# Esp_4relay_feedback.net
KiCad netlist of a schematic drawn in EAGLE
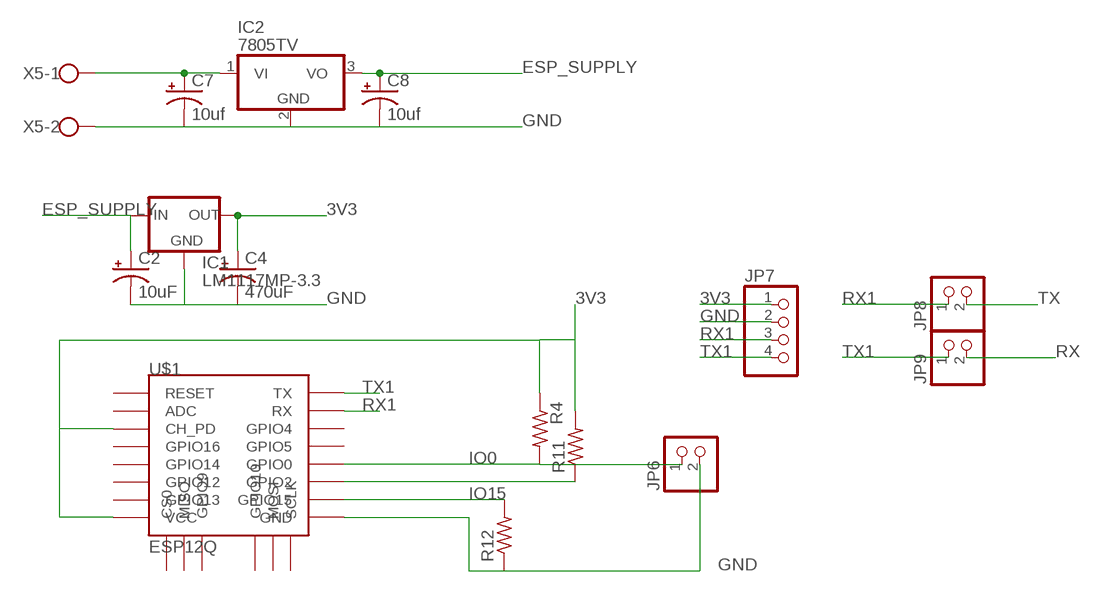
[diagram p0: schematic, sheet 1]
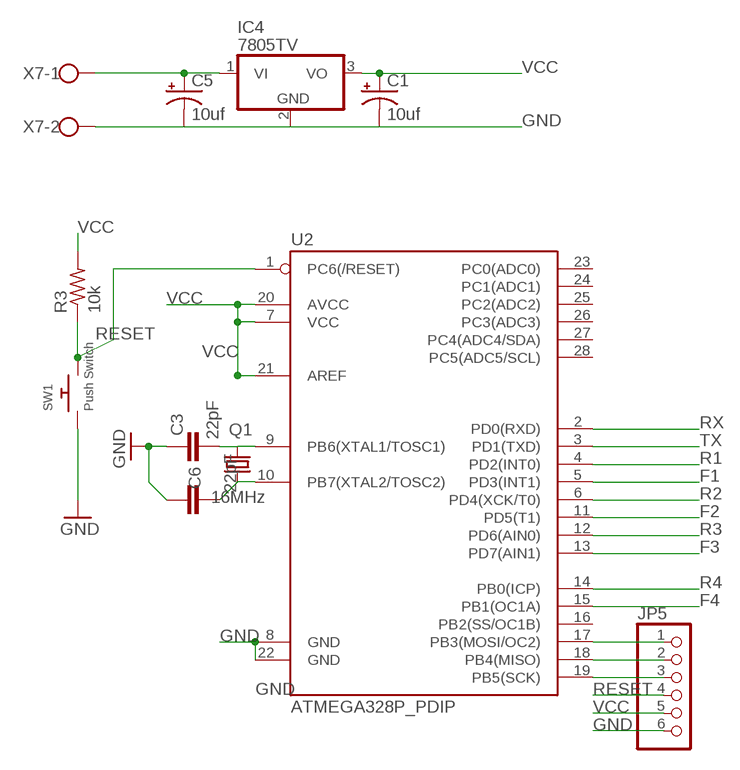
[diagram p1: schematic, sheet 2]
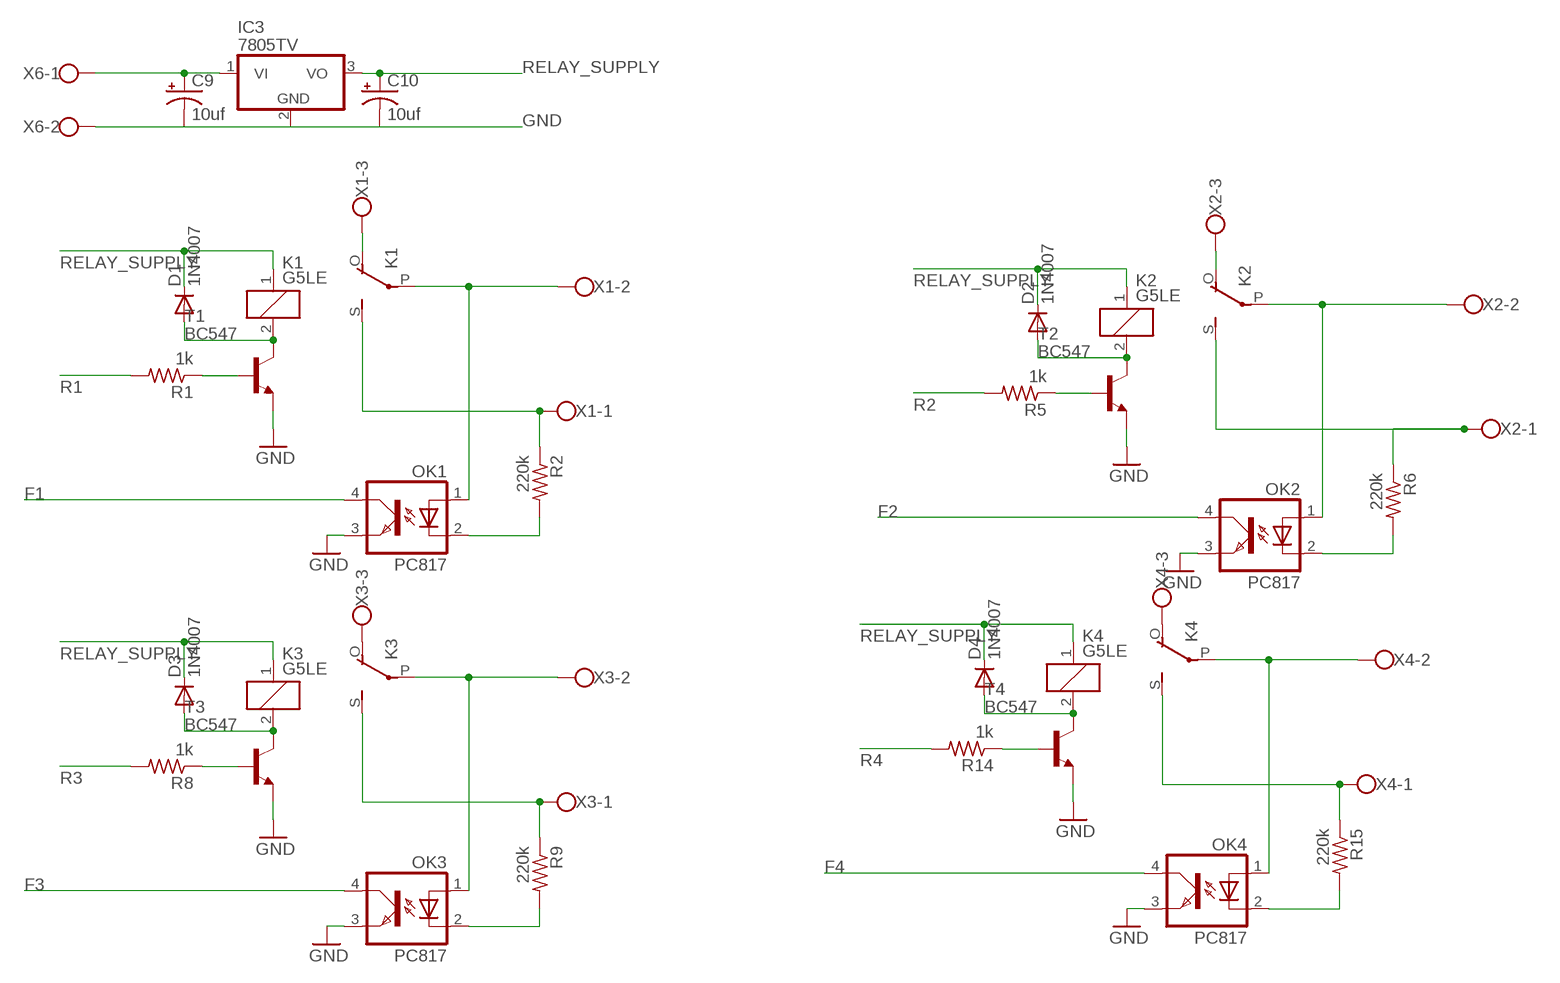
[diagram p2: schematic, sheet 3]

(export (version "E")
  (design (tool "Eeschema 10.0.6"))
  (components
    (comp (ref "C9")
      (value "10uf")
      (footprint "eagle-import:E2,5-6")
      (libsource (lib "eagle-import") (part "CPOL-USE2.5-6"))
    )
    (comp (ref "C10")
      (value "10uf")
      (footprint "eagle-import:E2,5-6")
      (libsource (lib "eagle-import") (part "CPOL-USE2.5-6"))
    )
    (comp (ref "D1")
      (value "1N4007")
      (footprint "eagle-import:DO41-10")
      (libsource (lib "eagle-import") (part "1N4004"))
    )
    (comp (ref "D2")
      (value "1N4007")
      (footprint "eagle-import:DO41-10")
      (libsource (lib "eagle-import") (part "1N4004"))
    )
    (comp (ref "D3")
      (value "1N4007")
      (footprint "eagle-import:DO41-10")
      (libsource (lib "eagle-import") (part "1N4004"))
    )
    (comp (ref "D4")
      (value "1N4007")
      (footprint "eagle-import:DO41-10")
      (libsource (lib "eagle-import") (part "1N4004"))
    )
    (comp (ref "IC3")
      (value "7805TV")
      (footprint "eagle-import:TO220V")
      (libsource (lib "eagle-import") (part "78TV05"))
    )
    (comp (ref "K1")
      (value "G5LE")
      (footprint "eagle-import:G5LE")
      (libsource (lib "eagle-import") (part "G5LE"))
    )
    (comp (ref "K2")
      (value "G5LE")
      (footprint "eagle-import:G5LE")
      (libsource (lib "eagle-import") (part "G5LE"))
    )
    (comp (ref "K3")
      (value "G5LE")
      (footprint "eagle-import:G5LE")
      (libsource (lib "eagle-import") (part "G5LE"))
    )
    (comp (ref "K4")
      (value "G5LE")
      (footprint "eagle-import:G5LE")
      (libsource (lib "eagle-import") (part "G5LE"))
    )
    (comp (ref "OK1")
      (value "PC817")
      (footprint "eagle-import:DIL04")
      (fields (field (name "MPN") "PC817X4J000F"))
      (libsource (lib "eagle-import") (part "PC817"))
    )
    (comp (ref "OK2")
      (value "PC817")
      (footprint "eagle-import:DIL04")
      (fields (field (name "MPN") "PC817X4J000F"))
      (libsource (lib "eagle-import") (part "PC817"))
    )
    (comp (ref "OK3")
      (value "PC817")
      (footprint "eagle-import:DIL04")
      (fields (field (name "MPN") "PC817X4J000F"))
      (libsource (lib "eagle-import") (part "PC817"))
    )
    (comp (ref "OK4")
      (value "PC817")
      (footprint "eagle-import:DIL04")
      (fields (field (name "MPN") "PC817X4J000F"))
      (libsource (lib "eagle-import") (part "PC817"))
    )
    (comp (ref "R1")
      (value "1k")
      (footprint "eagle-import:0207_10")
      (libsource (lib "eagle-import") (part "R-US_0207/10"))
    )
    (comp (ref "R2")
      (value "220k")
      (footprint "eagle-import:0207_10")
      (libsource (lib "eagle-import") (part "R-US_0207/10"))
    )
    (comp (ref "R5")
      (value "1k")
      (footprint "eagle-import:0207_10")
      (libsource (lib "eagle-import") (part "R-US_0207/10"))
    )
    (comp (ref "R6")
      (value "220k")
      (footprint "eagle-import:0207_10")
      (libsource (lib "eagle-import") (part "R-US_0207/10"))
    )
    (comp (ref "R8")
      (value "1k")
      (footprint "eagle-import:0207_10")
      (libsource (lib "eagle-import") (part "R-US_0207/10"))
    )
    (comp (ref "R9")
      (value "220k")
      (footprint "eagle-import:0207_10")
      (libsource (lib "eagle-import") (part "R-US_0207/10"))
    )
    (comp (ref "R14")
      (value "1k")
      (footprint "eagle-import:0207_10")
      (libsource (lib "eagle-import") (part "R-US_0207/10"))
    )
    (comp (ref "R15")
      (value "220k")
      (footprint "eagle-import:0207_10")
      (libsource (lib "eagle-import") (part "R-US_0207/10"))
    )
    (comp (ref "T1")
      (value "BC547")
      (footprint "eagle-import:TO92")
      (libsource (lib "eagle-import") (part "BC547"))
    )
    (comp (ref "T2")
      (value "BC547")
      (footprint "eagle-import:TO92")
      (libsource (lib "eagle-import") (part "BC547"))
    )
    (comp (ref "T3")
      (value "BC547")
      (footprint "eagle-import:TO92")
      (libsource (lib "eagle-import") (part "BC547"))
    )
    (comp (ref "T4")
      (value "BC547")
      (footprint "eagle-import:TO92")
      (libsource (lib "eagle-import") (part "BC547"))
    )
    (comp (ref "X1")
      (value "W237-103")
      (footprint "eagle-import:W237-103")
      (fields
        (field (name "MPN") "237-103")
        (field (name "MPN_1") "237-103")
        (field (name "OC_FARNELL") "unknown")
        (field (name "OC_NEWARK") "18M7116")
      )
      (libsource (lib "eagle-import") (part "W237-103"))
    )
    (comp (ref "X2")
      (value "W237-103")
      (footprint "eagle-import:W237-103")
      (fields
        (field (name "MPN") "237-103")
        (field (name "MPN_1") "237-103")
        (field (name "OC_FARNELL") "unknown")
        (field (name "OC_NEWARK") "18M7116")
      )
      (libsource (lib "eagle-import") (part "W237-103"))
    )
    (comp (ref "X3")
      (value "W237-103")
      (footprint "eagle-import:W237-103")
      (fields
        (field (name "MPN") "237-103")
        (field (name "MPN_1") "237-103")
        (field (name "OC_FARNELL") "unknown")
        (field (name "OC_NEWARK") "18M7116")
      )
      (libsource (lib "eagle-import") (part "W237-103"))
    )
    (comp (ref "X4")
      (value "W237-103")
      (footprint "eagle-import:W237-103")
      (fields
        (field (name "MPN") "237-103")
        (field (name "MPN_1") "237-103")
        (field (name "OC_FARNELL") "unknown")
        (field (name "OC_NEWARK") "18M7116")
      )
      (libsource (lib "eagle-import") (part "W237-103"))
    )
    (comp (ref "X6")
      (value "W237-102")
      (footprint "eagle-import:W237-102")
      (fields (field (name "MPN") "237-102"))
      (libsource (lib "eagle-import") (part "W237-102"))
    )
    (comp (ref "C2")
      (value "10uF")
      (footprint "eagle-import:E2,5-6")
      (libsource (lib "eagle-import") (part "CPOL-USE2.5-6"))
    )
    (comp (ref "C4")
      (value "470uF")
      (footprint "eagle-import:E5-8,5")
      (libsource (lib "eagle-import") (part "CPOL-USE5-8.5"))
    )
    (comp (ref "C7")
      (value "10uf")
      (footprint "eagle-import:E2,5-6")
      (libsource (lib "eagle-import") (part "CPOL-USE2.5-6"))
    )
    (comp (ref "C8")
      (value "10uf")
      (footprint "eagle-import:E2,5-6")
      (libsource (lib "eagle-import") (part "CPOL-USE2.5-6"))
    )
    (comp (ref "IC1")
      (value "LM1117MP-3.3")
      (footprint "eagle-import:SOT223")
      (fields (field (name "MF") "Texas Instruments"))
      (libsource (lib "eagle-import") (part "LM1117?-MP3.3"))
    )
    (comp (ref "IC2")
      (value "7805TV")
      (footprint "eagle-import:TO220V")
      (libsource (lib "eagle-import") (part "78TV05"))
    )
    (comp (ref "JP6")
      (value "PINHD-1X2")
      (footprint "eagle-import:1X02")
      (libsource (lib "eagle-import") (part "PINHD-1X2"))
    )
    (comp (ref "JP7")
      (value "PINHD-1X4")
      (footprint "eagle-import:1X04")
      (libsource (lib "eagle-import") (part "PINHD-1X4"))
    )
    (comp (ref "JP8")
      (value "PINHD-1X2")
      (footprint "eagle-import:1X02")
      (libsource (lib "eagle-import") (part "PINHD-1X2"))
    )
    (comp (ref "JP9")
      (value "PINHD-1X2")
      (footprint "eagle-import:1X02")
      (libsource (lib "eagle-import") (part "PINHD-1X2"))
    )
    (comp (ref "R4")
      (value "R-US_0207/10")
      (footprint "eagle-import:0207_10")
      (libsource (lib "eagle-import") (part "R-US_0207/10"))
    )
    (comp (ref "R11")
      (value "R-US_0207/10")
      (footprint "eagle-import:0207_10")
      (libsource (lib "eagle-import") (part "R-US_0207/10"))
    )
    (comp (ref "R12")
      (value "R-US_0207/10")
      (footprint "eagle-import:0207_10")
      (libsource (lib "eagle-import") (part "R-US_0207/10"))
    )
    (comp (ref "U$1")
      (value "ESP12Q")
      (footprint "eagle-import:ESP12Q")
      (libsource (lib "eagle-import") (part "ESP12Q"))
    )
    (comp (ref "X5")
      (value "W237-102")
      (footprint "eagle-import:W237-102")
      (fields (field (name "MPN") "237-102"))
      (libsource (lib "eagle-import") (part "W237-102"))
    )
    (comp (ref "C1")
      (value "10uf")
      (footprint "eagle-import:E2,5-6")
      (libsource (lib "eagle-import") (part "CPOL-USE2.5-6"))
    )
    (comp (ref "C3")
      (value "22pF")
      (footprint "eagle-import:CAP-PTH-SMALL")
      (libsource (lib "eagle-import") (part "CAPPTH"))
    )
    (comp (ref "C5")
      (value "10uf")
      (footprint "eagle-import:E2,5-6")
      (libsource (lib "eagle-import") (part "CPOL-USE2.5-6"))
    )
    (comp (ref "C6")
      (value "22pF")
      (footprint "eagle-import:CAP-PTH-SMALL")
      (libsource (lib "eagle-import") (part "CAPPTH"))
    )
    (comp (ref "IC4")
      (value "7805TV")
      (footprint "eagle-import:TO220V")
      (libsource (lib "eagle-import") (part "78TV05"))
    )
    (comp (ref "JP5")
      (value "PINHD-1X6")
      (footprint "eagle-import:1X06")
      (libsource (lib "eagle-import") (part "PINHD-1X6"))
    )
    (comp (ref "Q1")
      (value "16MHz")
      (footprint "eagle-import:HC49US")
      (libsource (lib "eagle-import") (part "CRYSTALHC49US"))
    )
    (comp (ref "R3")
      (value "10k")
      (footprint "eagle-import:0207_10")
      (libsource (lib "eagle-import") (part "resistor_R-US_0207/10"))
    )
    (comp (ref "SW1")
      (value "Push Switch")
      (footprint "eagle-import:TACT_PANA-EVQ")
      (libsource (lib "eagle-import") (part "SWITCH_PUSHBUTTONEVQ-PE"))
    )
    (comp (ref "U2")
      (value "ATMEGA328P_PDIP")
      (footprint "eagle-import:DIL28-3")
      (libsource (lib "eagle-import") (part "ATMEGA328P_PDIP"))
    )
    (comp (ref "X7")
      (value "W237-102")
      (footprint "eagle-import:W237-102")
      (fields (field (name "MPN") "237-102"))
      (libsource (lib "eagle-import") (part "W237-102"))
    )
  )
  (nets
    (net (code "1") (name "3V3") (class "Default")
      (node (ref "C4") (pin "+") (pinfunction "+_+") (pintype "passive"))
      (node (ref "IC1") (pin "2") (pinfunction "OUT_2") (pintype "passive"))
      (node (ref "IC1") (pin "4") (pinfunction "OUT_4") (pintype "passive"))
      (node (ref "JP7") (pin "1") (pinfunction "1_1") (pintype "passive"))
      (node (ref "R11") (pin "2") (pinfunction "2_2") (pintype "passive"))
      (node (ref "R4") (pin "1") (pinfunction "1_1") (pintype "passive"))
      (node (ref "U$1") (pin "CH_PD") (pinfunction "CH_PD_CH_PD") (pintype "bidirectional"))
      (node (ref "U$1") (pin "VCC") (pinfunction "VCC_VCC") (pintype "bidirectional"))
    )
    (net (code "2") (name "ESP_SUPPLY") (class "Default")
      (node (ref "C2") (pin "+") (pinfunction "+_+") (pintype "passive"))
      (node (ref "C8") (pin "+") (pinfunction "+_+") (pintype "passive"))
      (node (ref "IC1") (pin "3") (pinfunction "IN_3") (pintype "input"))
      (node (ref "IC2") (pin "3") (pinfunction "VO_3") (pintype "passive"))
    )
    (net (code "3") (name "F1") (class "Default")
      (node (ref "OK1") (pin "4") (pinfunction "COL_4") (pintype "passive"))
      (node (ref "U2") (pin "5") (pinfunction "PD3(INT1)_5") (pintype "bidirectional"))
    )
    (net (code "4") (name "F2") (class "Default")
      (node (ref "OK2") (pin "4") (pinfunction "COL_4") (pintype "passive"))
      (node (ref "U2") (pin "11") (pinfunction "PD5(T1)_11") (pintype "bidirectional"))
    )
    (net (code "5") (name "F3") (class "Default")
      (node (ref "OK3") (pin "4") (pinfunction "COL_4") (pintype "passive"))
      (node (ref "U2") (pin "13") (pinfunction "PD7(AIN1)_13") (pintype "bidirectional"))
    )
    (net (code "6") (name "F4") (class "Default")
      (node (ref "OK4") (pin "4") (pinfunction "COL_4") (pintype "passive"))
      (node (ref "U2") (pin "15") (pinfunction "PB1(OC1A)_15") (pintype "bidirectional"))
    )
    (net (code "7") (name "GND") (class "Default")
      (node (ref "C1") (pin "-") (pinfunction "-_-") (pintype "passive"))
      (node (ref "C10") (pin "-") (pinfunction "-_-") (pintype "passive"))
      (node (ref "C2") (pin "-") (pinfunction "-_-") (pintype "passive"))
      (node (ref "C3") (pin "1") (pinfunction "1_1") (pintype "passive"))
      (node (ref "C4") (pin "-") (pinfunction "-_-") (pintype "passive"))
      (node (ref "C5") (pin "-") (pinfunction "-_-") (pintype "passive"))
      (node (ref "C6") (pin "1") (pinfunction "1_1") (pintype "passive"))
      (node (ref "C7") (pin "-") (pinfunction "-_-") (pintype "passive"))
      (node (ref "C8") (pin "-") (pinfunction "-_-") (pintype "passive"))
      (node (ref "C9") (pin "-") (pinfunction "-_-") (pintype "passive"))
      (node (ref "IC1") (pin "1") (pinfunction "GND_1") (pintype "input"))
      (node (ref "IC2") (pin "2") (pinfunction "GND_2") (pintype "passive"))
      (node (ref "IC3") (pin "2") (pinfunction "GND_2") (pintype "passive"))
      (node (ref "IC4") (pin "2") (pinfunction "GND_2") (pintype "passive"))
      (node (ref "JP5") (pin "6") (pinfunction "6_6") (pintype "passive"))
      (node (ref "JP6") (pin "2") (pinfunction "2_2") (pintype "passive"))
      (node (ref "JP7") (pin "2") (pinfunction "2_2") (pintype "passive"))
      (node (ref "OK1") (pin "3") (pinfunction "EMIT_3") (pintype "passive"))
      (node (ref "OK2") (pin "3") (pinfunction "EMIT_3") (pintype "passive"))
      (node (ref "OK3") (pin "3") (pinfunction "EMIT_3") (pintype "passive"))
      (node (ref "OK4") (pin "3") (pinfunction "EMIT_3") (pintype "passive"))
      (node (ref "R12") (pin "1") (pinfunction "1_1") (pintype "passive"))
      (node (ref "SW1") (pin "P$1") (pinfunction "P$1_P$1") (pintype "passive"))
      (node (ref "T1") (pin "1") (pinfunction "E_1") (pintype "passive"))
      (node (ref "T2") (pin "1") (pinfunction "E_1") (pintype "passive"))
      (node (ref "T3") (pin "1") (pinfunction "E_1") (pintype "passive"))
      (node (ref "T4") (pin "1") (pinfunction "E_1") (pintype "passive"))
      (node (ref "U$1") (pin "GND") (pinfunction "GND_GND") (pintype "bidirectional"))
      (node (ref "U2") (pin "22") (pinfunction "GND_22") (pintype "bidirectional"))
      (node (ref "U2") (pin "8") (pinfunction "GND_8") (pintype "bidirectional"))
      (node (ref "X5") (pin "2") (pinfunction "KL_2") (pintype "passive"))
      (node (ref "X6") (pin "2") (pinfunction "KL_2") (pintype "passive"))
      (node (ref "X7") (pin "2") (pinfunction "KL_2") (pintype "passive"))
    )
    (net (code "8") (name "IO0") (class "Default")
      (node (ref "JP6") (pin "1") (pinfunction "1_1") (pintype "passive"))
      (node (ref "R4") (pin "2") (pinfunction "2_2") (pintype "passive"))
      (node (ref "U$1") (pin "GPIO0") (pinfunction "GPIO0_GPIO0") (pintype "bidirectional"))
    )
    (net (code "9") (name "IO15") (class "Default")
      (node (ref "R12") (pin "2") (pinfunction "2_2") (pintype "passive"))
      (node (ref "U$1") (pin "GPIO15") (pinfunction "GPIO15_GPIO15") (pintype "bidirectional"))
    )
    (net (code "10") (name "Net-(IC2-VI)") (class "Default")
      (node (ref "C7") (pin "+") (pinfunction "+_+") (pintype "passive"))
      (node (ref "IC2") (pin "1") (pinfunction "VI_1") (pintype "input"))
      (node (ref "X5") (pin "1") (pinfunction "KL_1") (pintype "passive"))
    )
    (net (code "11") (name "Net-(IC3-VI)") (class "Default")
      (node (ref "C9") (pin "+") (pinfunction "+_+") (pintype "passive"))
      (node (ref "IC3") (pin "1") (pinfunction "VI_1") (pintype "input"))
      (node (ref "X6") (pin "1") (pinfunction "KL_1") (pintype "passive"))
    )
    (net (code "12") (name "Net-(IC4-VI)") (class "Default")
      (node (ref "C5") (pin "+") (pinfunction "+_+") (pintype "passive"))
      (node (ref "IC4") (pin "1") (pinfunction "VI_1") (pintype "input"))
      (node (ref "X7") (pin "1") (pinfunction "KL_1") (pintype "passive"))
    )
    (net (code "13") (name "Net-(OK1-A)") (class "Default")
      (node (ref "K1") (pin "P") (pinfunction "P_P") (pintype "passive"))
      (node (ref "OK1") (pin "1") (pinfunction "A_1") (pintype "passive"))
      (node (ref "X1") (pin "2") (pinfunction "KL_2") (pintype "passive"))
    )
    (net (code "14") (name "Net-(OK1-C)") (class "Default")
      (node (ref "OK1") (pin "2") (pinfunction "C_2") (pintype "passive"))
      (node (ref "R2") (pin "2") (pinfunction "2_2") (pintype "passive"))
    )
    (net (code "15") (name "Net-(OK2-A)") (class "Default")
      (node (ref "K2") (pin "P") (pinfunction "P_P") (pintype "passive"))
      (node (ref "OK2") (pin "1") (pinfunction "A_1") (pintype "passive"))
      (node (ref "X2") (pin "2") (pinfunction "KL_2") (pintype "passive"))
    )
    (net (code "16") (name "Net-(OK2-C)") (class "Default")
      (node (ref "OK2") (pin "2") (pinfunction "C_2") (pintype "passive"))
      (node (ref "R6") (pin "2") (pinfunction "2_2") (pintype "passive"))
    )
    (net (code "17") (name "Net-(OK3-A)") (class "Default")
      (node (ref "K3") (pin "P") (pinfunction "P_P") (pintype "passive"))
      (node (ref "OK3") (pin "1") (pinfunction "A_1") (pintype "passive"))
      (node (ref "X3") (pin "2") (pinfunction "KL_2") (pintype "passive"))
    )
    (net (code "18") (name "Net-(OK3-C)") (class "Default")
      (node (ref "OK3") (pin "2") (pinfunction "C_2") (pintype "passive"))
      (node (ref "R9") (pin "2") (pinfunction "2_2") (pintype "passive"))
    )
    (net (code "19") (name "Net-(OK4-A)") (class "Default")
      (node (ref "K4") (pin "P") (pinfunction "P_P") (pintype "passive"))
      (node (ref "OK4") (pin "1") (pinfunction "A_1") (pintype "passive"))
      (node (ref "X4") (pin "2") (pinfunction "KL_2") (pintype "passive"))
    )
    (net (code "20") (name "Net-(OK4-C)") (class "Default")
      (node (ref "OK4") (pin "2") (pinfunction "C_2") (pintype "passive"))
      (node (ref "R15") (pin "2") (pinfunction "2_2") (pintype "passive"))
    )
    (net (code "21") (name "Net-(R11-Pad1)") (class "Default")
      (node (ref "R11") (pin "1") (pinfunction "1_1") (pintype "passive"))
      (node (ref "U$1") (pin "GPIO2") (pinfunction "GPIO2_GPIO2") (pintype "bidirectional"))
    )
    (net (code "22") (name "Net-(T1-B)") (class "Default")
      (node (ref "R1") (pin "1") (pinfunction "1_1") (pintype "passive"))
      (node (ref "T1") (pin "2") (pinfunction "B_2") (pintype "passive"))
    )
    (net (code "23") (name "Net-(T1-C)") (class "Default")
      (node (ref "D1") (pin "A") (pinfunction "A_A") (pintype "passive"))
      (node (ref "K1") (pin "2") (pinfunction "2_2") (pintype "passive"))
      (node (ref "T1") (pin "3") (pinfunction "C_3") (pintype "passive"))
    )
    (net (code "24") (name "Net-(T2-B)") (class "Default")
      (node (ref "R5") (pin "1") (pinfunction "1_1") (pintype "passive"))
      (node (ref "T2") (pin "2") (pinfunction "B_2") (pintype "passive"))
    )
    (net (code "25") (name "Net-(T2-C)") (class "Default")
      (node (ref "D2") (pin "A") (pinfunction "A_A") (pintype "passive"))
      (node (ref "K2") (pin "2") (pinfunction "2_2") (pintype "passive"))
      (node (ref "T2") (pin "3") (pinfunction "C_3") (pintype "passive"))
    )
    (net (code "26") (name "Net-(T3-B)") (class "Default")
      (node (ref "R8") (pin "1") (pinfunction "1_1") (pintype "passive"))
      (node (ref "T3") (pin "2") (pinfunction "B_2") (pintype "passive"))
    )
    (net (code "27") (name "Net-(T3-C)") (class "Default")
      (node (ref "D3") (pin "A") (pinfunction "A_A") (pintype "passive"))
      (node (ref "K3") (pin "2") (pinfunction "2_2") (pintype "passive"))
      (node (ref "T3") (pin "3") (pinfunction "C_3") (pintype "passive"))
    )
    (net (code "28") (name "Net-(T4-B)") (class "Default")
      (node (ref "R14") (pin "1") (pinfunction "1_1") (pintype "passive"))
      (node (ref "T4") (pin "2") (pinfunction "B_2") (pintype "passive"))
    )
    (net (code "29") (name "Net-(T4-C)") (class "Default")
      (node (ref "D4") (pin "A") (pinfunction "A_A") (pintype "passive"))
      (node (ref "K4") (pin "2") (pinfunction "2_2") (pintype "passive"))
      (node (ref "T4") (pin "3") (pinfunction "C_3") (pintype "passive"))
    )
    (net (code "30") (name "Net-(U2-PB3(MOSI{slash}OC2))") (class "Default")
      (node (ref "JP5") (pin "1") (pinfunction "1_1") (pintype "passive"))
      (node (ref "U2") (pin "17") (pinfunction "PB3(MOSI/OC2)_17") (pintype "bidirectional"))
    )
    (net (code "31") (name "Net-(U2-PB4(MISO))") (class "Default")
      (node (ref "JP5") (pin "2") (pinfunction "2_2") (pintype "passive"))
      (node (ref "U2") (pin "18") (pinfunction "PB4(MISO)_18") (pintype "bidirectional"))
    )
    (net (code "32") (name "Net-(U2-PB5(SCK))") (class "Default")
      (node (ref "JP5") (pin "3") (pinfunction "3_3") (pintype "passive"))
      (node (ref "U2") (pin "19") (pinfunction "PB5(SCK)_19") (pintype "bidirectional"))
    )
    (net (code "33") (name "Net-(U2-PB6(XTAL1{slash}TOSC1))") (class "Default")
      (node (ref "C3") (pin "2") (pinfunction "2_2") (pintype "passive"))
      (node (ref "Q1") (pin "2") (pinfunction "2_2") (pintype "passive"))
      (node (ref "U2") (pin "9") (pinfunction "PB6(XTAL1/TOSC1)_9") (pintype "bidirectional"))
    )
    (net (code "34") (name "Net-(U2-PB7(XTAL2{slash}TOSC2))") (class "Default")
      (node (ref "C6") (pin "2") (pinfunction "2_2") (pintype "passive"))
      (node (ref "Q1") (pin "1") (pinfunction "1_1") (pintype "passive"))
      (node (ref "U2") (pin "10") (pinfunction "PB7(XTAL2/TOSC2)_10") (pintype "bidirectional"))
    )
    (net (code "35") (name "Net-(X1A-KL)") (class "Default")
      (node (ref "K1") (pin "S") (pinfunction "S_S") (pintype "passive"))
      (node (ref "R2") (pin "1") (pinfunction "1_1") (pintype "passive"))
      (node (ref "X1") (pin "1") (pinfunction "KL_1") (pintype "passive"))
    )
    (net (code "36") (name "Net-(X1C-KL)") (class "Default")
      (node (ref "K1") (pin "O") (pinfunction "O_O") (pintype "passive"))
      (node (ref "X1") (pin "3") (pinfunction "KL_3") (pintype "passive"))
    )
    (net (code "37") (name "Net-(X2A-KL)") (class "Default")
      (node (ref "K2") (pin "S") (pinfunction "S_S") (pintype "passive"))
      (node (ref "R6") (pin "1") (pinfunction "1_1") (pintype "passive"))
      (node (ref "X2") (pin "1") (pinfunction "KL_1") (pintype "passive"))
    )
    (net (code "38") (name "Net-(X2C-KL)") (class "Default")
      (node (ref "K2") (pin "O") (pinfunction "O_O") (pintype "passive"))
      (node (ref "X2") (pin "3") (pinfunction "KL_3") (pintype "passive"))
    )
    (net (code "39") (name "Net-(X3A-KL)") (class "Default")
      (node (ref "K3") (pin "S") (pinfunction "S_S") (pintype "passive"))
      (node (ref "R9") (pin "1") (pinfunction "1_1") (pintype "passive"))
      (node (ref "X3") (pin "1") (pinfunction "KL_1") (pintype "passive"))
    )
    (net (code "40") (name "Net-(X3C-KL)") (class "Default")
      (node (ref "K3") (pin "O") (pinfunction "O_O") (pintype "passive"))
      (node (ref "X3") (pin "3") (pinfunction "KL_3") (pintype "passive"))
    )
    (net (code "41") (name "Net-(X4A-KL)") (class "Default")
      (node (ref "K4") (pin "S") (pinfunction "S_S") (pintype "passive"))
      (node (ref "R15") (pin "1") (pinfunction "1_1") (pintype "passive"))
      (node (ref "X4") (pin "1") (pinfunction "KL_1") (pintype "passive"))
    )
    (net (code "42") (name "Net-(X4C-KL)") (class "Default")
      (node (ref "K4") (pin "O") (pinfunction "O_O") (pintype "passive"))
      (node (ref "X4") (pin "3") (pinfunction "KL_3") (pintype "passive"))
    )
    (net (code "43") (name "R1") (class "Default")
      (node (ref "R1") (pin "2") (pinfunction "2_2") (pintype "passive"))
      (node (ref "U2") (pin "4") (pinfunction "PD2(INT0)_4") (pintype "bidirectional"))
    )
    (net (code "44") (name "R2") (class "Default")
      (node (ref "R5") (pin "2") (pinfunction "2_2") (pintype "passive"))
      (node (ref "U2") (pin "6") (pinfunction "PD4(XCK/T0)_6") (pintype "bidirectional"))
    )
    (net (code "45") (name "R3") (class "Default")
      (node (ref "R8") (pin "2") (pinfunction "2_2") (pintype "passive"))
      (node (ref "U2") (pin "12") (pinfunction "PD6(AIN0)_12") (pintype "bidirectional"))
    )
    (net (code "46") (name "R4") (class "Default")
      (node (ref "R14") (pin "2") (pinfunction "2_2") (pintype "passive"))
      (node (ref "U2") (pin "14") (pinfunction "PB0(ICP)_14") (pintype "bidirectional"))
    )
    (net (code "47") (name "RELAY_SUPPLY") (class "Default")
      (node (ref "C10") (pin "+") (pinfunction "+_+") (pintype "passive"))
      (node (ref "D1") (pin "C") (pinfunction "C_C") (pintype "passive"))
      (node (ref "D2") (pin "C") (pinfunction "C_C") (pintype "passive"))
      (node (ref "D3") (pin "C") (pinfunction "C_C") (pintype "passive"))
      (node (ref "D4") (pin "C") (pinfunction "C_C") (pintype "passive"))
      (node (ref "IC3") (pin "3") (pinfunction "VO_3") (pintype "passive"))
      (node (ref "K1") (pin "1") (pinfunction "1_1") (pintype "passive"))
      (node (ref "K2") (pin "1") (pinfunction "1_1") (pintype "passive"))
      (node (ref "K3") (pin "1") (pinfunction "1_1") (pintype "passive"))
      (node (ref "K4") (pin "1") (pinfunction "1_1") (pintype "passive"))
    )
    (net (code "48") (name "RESET") (class "Default")
      (node (ref "JP5") (pin "4") (pinfunction "4_4") (pintype "passive"))
      (node (ref "R3") (pin "1") (pinfunction "1_1") (pintype "passive"))
      (node (ref "SW1") (pin "P$2") (pinfunction "P$2_P$2") (pintype "passive"))
      (node (ref "U2") (pin "1") (pinfunction "PC6(/RESET)_1") (pintype "bidirectional"))
    )
    (net (code "49") (name "RX") (class "Default")
      (node (ref "JP9") (pin "2") (pinfunction "2_2") (pintype "passive"))
      (node (ref "U2") (pin "2") (pinfunction "PD0(RXD)_2") (pintype "bidirectional"))
    )
    (net (code "50") (name "RX1") (class "Default")
      (node (ref "JP7") (pin "3") (pinfunction "3_3") (pintype "passive"))
      (node (ref "JP8") (pin "1") (pinfunction "1_1") (pintype "passive"))
      (node (ref "U$1") (pin "RX") (pinfunction "RX_RX") (pintype "bidirectional"))
    )
    (net (code "51") (name "TX") (class "Default")
      (node (ref "JP8") (pin "2") (pinfunction "2_2") (pintype "passive"))
      (node (ref "U2") (pin "3") (pinfunction "PD1(TXD)_3") (pintype "bidirectional"))
    )
    (net (code "52") (name "TX1") (class "Default")
      (node (ref "JP7") (pin "4") (pinfunction "4_4") (pintype "passive"))
      (node (ref "JP9") (pin "1") (pinfunction "1_1") (pintype "passive"))
      (node (ref "U$1") (pin "TX") (pinfunction "TX_TX") (pintype "bidirectional"))
    )
    (net (code "53") (name "VCC") (class "Default")
      (node (ref "C1") (pin "+") (pinfunction "+_+") (pintype "passive"))
      (node (ref "IC4") (pin "3") (pinfunction "VO_3") (pintype "passive"))
      (node (ref "JP5") (pin "5") (pinfunction "5_5") (pintype "passive"))
      (node (ref "R3") (pin "2") (pinfunction "2_2") (pintype "passive"))
      (node (ref "U2") (pin "20") (pinfunction "AVCC_20") (pintype "bidirectional"))
      (node (ref "U2") (pin "21") (pinfunction "AREF_21") (pintype "bidirectional"))
      (node (ref "U2") (pin "7") (pinfunction "VCC_7") (pintype "bidirectional"))
    )
    (net (code "54") (name "unconnected-(U$1-PadADC)") (class "Default")
      (node (ref "U$1") (pin "ADC") (pinfunction "ADC_ADC") (pintype "bidirectional"))
    )
    (net (code "55") (name "unconnected-(U$1-PadCS0)") (class "Default")
      (node (ref "U$1") (pin "CS0") (pinfunction "CS0_CS0") (pintype "bidirectional"))
    )
    (net (code "56") (name "unconnected-(U$1-PadGPIO4)") (class "Default")
      (node (ref "U$1") (pin "GPIO4") (pinfunction "GPIO4_GPIO4") (pintype "bidirectional"))
    )
    (net (code "57") (name "unconnected-(U$1-PadGPIO5)") (class "Default")
      (node (ref "U$1") (pin "GPIO5") (pinfunction "GPIO5_GPIO5") (pintype "bidirectional"))
    )
    (net (code "58") (name "unconnected-(U$1-PadGPIO9)") (class "Default")
      (node (ref "U$1") (pin "GPIO9") (pinfunction "GPIO9_GPIO9") (pintype "bidirectional"))
    )
    (net (code "59") (name "unconnected-(U$1-PadGPIO10)") (class "Default")
      (node (ref "U$1") (pin "GPIO10") (pinfunction "GPIO10_GPIO10") (pintype "bidirectional"))
    )
    (net (code "60") (name "unconnected-(U$1-PadGPIO12)") (class "Default")
      (node (ref "U$1") (pin "GPIO12") (pinfunction "GPIO12_GPIO12") (pintype "bidirectional"))
    )
    (net (code "61") (name "unconnected-(U$1-PadGPIO13)") (class "Default")
      (node (ref "U$1") (pin "GPIO13") (pinfunction "GPIO13_GPIO13") (pintype "bidirectional"))
    )
    (net (code "62") (name "unconnected-(U$1-PadGPIO14)") (class "Default")
      (node (ref "U$1") (pin "GPIO14") (pinfunction "GPIO14_GPIO14") (pintype "bidirectional"))
    )
    (net (code "63") (name "unconnected-(U$1-PadGPIO16)") (class "Default")
      (node (ref "U$1") (pin "GPIO16") (pinfunction "GPIO16_GPIO16") (pintype "bidirectional"))
    )
    (net (code "64") (name "unconnected-(U$1-PadMISO)") (class "Default")
      (node (ref "U$1") (pin "MISO") (pinfunction "MISO_MISO") (pintype "bidirectional"))
    )
    (net (code "65") (name "unconnected-(U$1-PadMOSI)") (class "Default")
      (node (ref "U$1") (pin "MOSI") (pinfunction "MOSI_MOSI") (pintype "bidirectional"))
    )
    (net (code "66") (name "unconnected-(U$1-PadRESET)") (class "Default")
      (node (ref "U$1") (pin "RESET") (pinfunction "RESET_RESET") (pintype "bidirectional"))
    )
    (net (code "67") (name "unconnected-(U$1-PadSCLK)") (class "Default")
      (node (ref "U$1") (pin "SCLK") (pinfunction "SCLK_SCLK") (pintype "bidirectional"))
    )
    (net (code "68") (name "unconnected-(U2-PB2(SS{slash}OC1B)-Pad16)") (class "Default")
      (node (ref "U2") (pin "16") (pinfunction "PB2(SS/OC1B)_16") (pintype "bidirectional"))
    )
    (net (code "69") (name "unconnected-(U2-PC0(ADC0)-Pad23)") (class "Default")
      (node (ref "U2") (pin "23") (pinfunction "PC0(ADC0)_23") (pintype "bidirectional"))
    )
    (net (code "70") (name "unconnected-(U2-PC1(ADC1)-Pad24)") (class "Default")
      (node (ref "U2") (pin "24") (pinfunction "PC1(ADC1)_24") (pintype "bidirectional"))
    )
    (net (code "71") (name "unconnected-(U2-PC2(ADC2)-Pad25)") (class "Default")
      (node (ref "U2") (pin "25") (pinfunction "PC2(ADC2)_25") (pintype "bidirectional"))
    )
    (net (code "72") (name "unconnected-(U2-PC3(ADC3)-Pad26)") (class "Default")
      (node (ref "U2") (pin "26") (pinfunction "PC3(ADC3)_26") (pintype "bidirectional"))
    )
    (net (code "73") (name "unconnected-(U2-PC4(ADC4{slash}SDA)-Pad27)") (class "Default")
      (node (ref "U2") (pin "27") (pinfunction "PC4(ADC4/SDA)_27") (pintype "bidirectional"))
    )
    (net (code "74") (name "unconnected-(U2-PC5(ADC5{slash}SCL)-Pad28)") (class "Default")
      (node (ref "U2") (pin "28") (pinfunction "PC5(ADC5/SCL)_28") (pintype "bidirectional"))
    )
  )
)
